# 02_ESP12_CORE.net
KiCad netlist of a schematic drawn in Altium Designer
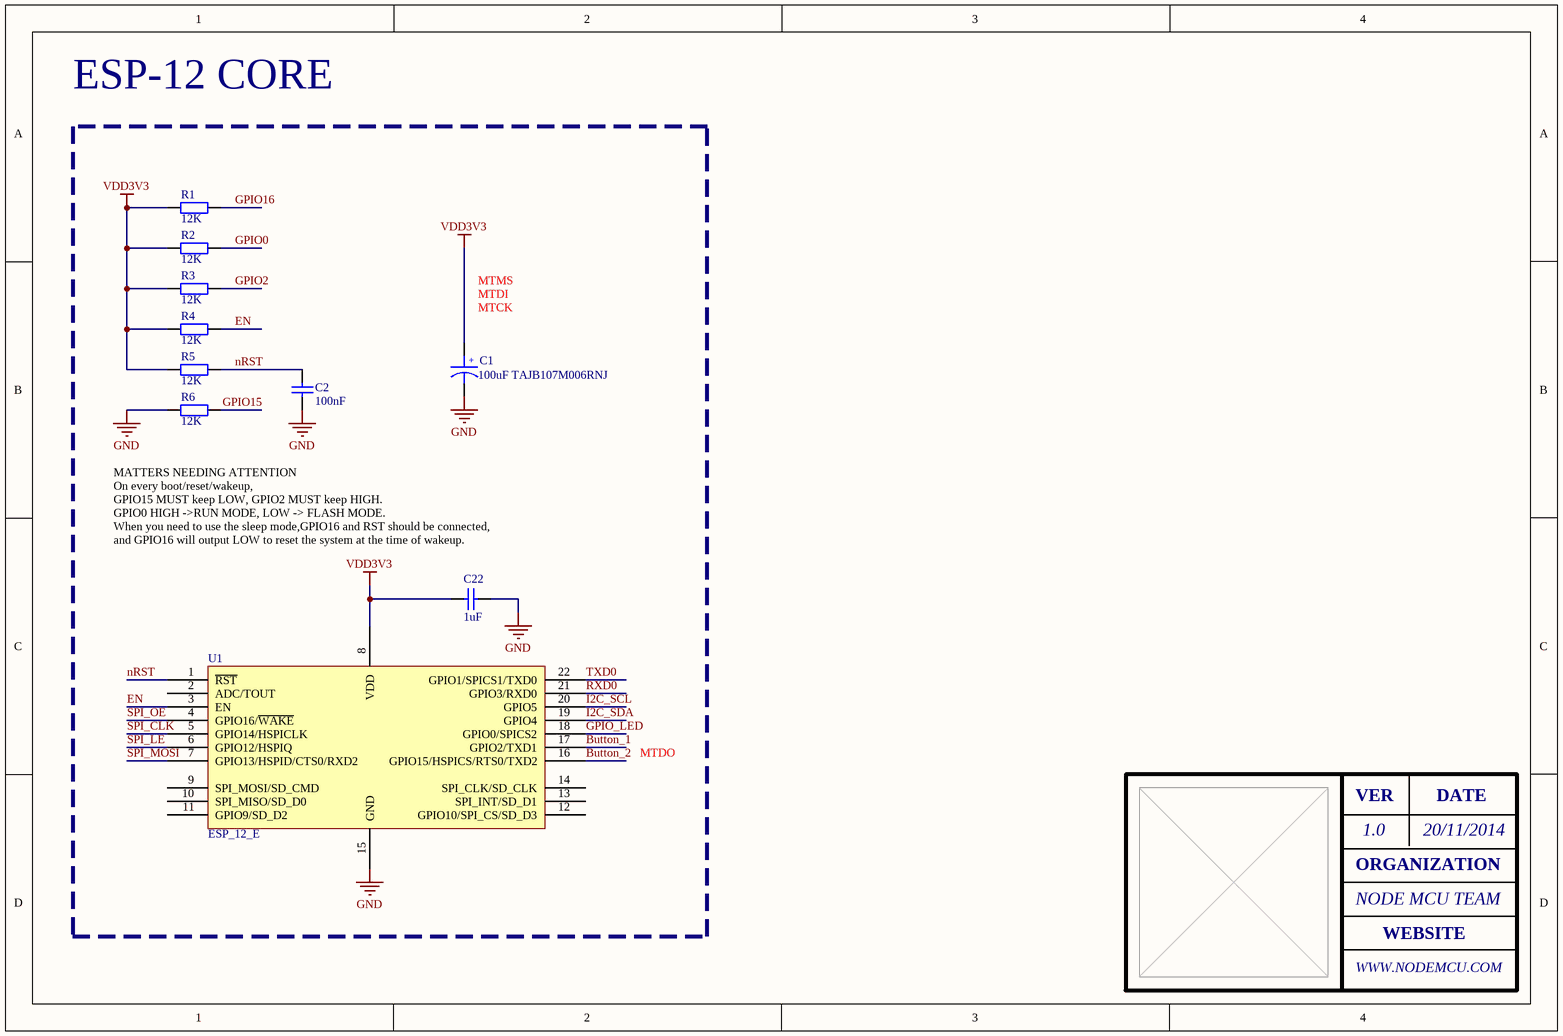
[diagram p0: 02_ESP12_CORE.SchDoc]

(export (version "E")
  (design (tool "Eeschema 10.0.6"))
  (components
    (comp (ref "C1")
      (value "100uF TAJB107M006RNJ")
      (footprint "FP_Tantal_D")
      (description "Capacitor, SM Tantalum; Body 3.5 x 2.8 mm (LxW typ)")
      (libsource (lib "Vowstar_Basic_Device") (part "SMT_C_Tantalum_B"))
    )
    (comp (ref "C2")
      (value "100nF")
      (footprint "FP_0805_CAP_085")
      (description "Capacitor")
      (fields (field (name "TOLERANCE") "+80%/-20%") (field (name "VOLTAGE") "25V"))
      (libsource (lib "onlablib") (part "CAP 100nF"))
    )
    (comp (ref "C22")
      (value "1uF")
      (footprint "6-0805_M")
      (description "Capacitor")
      (fields (field (name "TOLERANCE") "+80%/-20%") (field (name "VOLTAGE") "25V"))
      (libsource (lib "onlablib") (part "CAP 1uF"))
    )
    (comp (ref "R1")
      (value "12K")
      (footprint "FP_0805_RES")
      (description "Resistor")
      (fields (field (name "TOLERANCE") "5%") (field (name "POWER") "125mW"))
      (libsource (lib "onlablib") (part "RES 12K"))
    )
    (comp (ref "R2")
      (value "12K")
      (footprint "FP_0805_RES")
      (description "Resistor")
      (fields (field (name "TOLERANCE") "5%") (field (name "POWER") "125mW"))
      (libsource (lib "onlablib") (part "RES 12K"))
    )
    (comp (ref "R3")
      (value "12K")
      (footprint "FP_0805_RES")
      (description "Resistor")
      (fields (field (name "TOLERANCE") "5%") (field (name "POWER") "125mW"))
      (libsource (lib "onlablib") (part "RES 12K"))
    )
    (comp (ref "R4")
      (value "12K")
      (footprint "FP_0805_RES")
      (description "Resistor")
      (fields (field (name "TOLERANCE") "5%") (field (name "POWER") "125mW"))
      (libsource (lib "onlablib") (part "RES 12K"))
    )
    (comp (ref "R5")
      (value "12K")
      (footprint "FP_0805_RES")
      (description "Resistor")
      (fields (field (name "TOLERANCE") "5%") (field (name "POWER") "125mW"))
      (libsource (lib "onlablib") (part "RES 12K"))
    )
    (comp (ref "R6")
      (value "12K")
      (footprint "FP_0805_RES")
      (description "Resistor")
      (fields (field (name "TOLERANCE") "5%") (field (name "POWER") "125mW"))
      (libsource (lib "onlablib") (part "RES 12K"))
    )
    (comp (ref "U1")
      (value "ESP_12_E")
      (footprint "ESP_12_E _widepad")
      (description "ESP-12 Wi-Fi Module by AI-Thinker")
      (libsource (lib "Vowstar_Module") (part "ESP_12_E"))
    )
  )
  (nets
    (net (code "1") (name "/Button_1") (class "Default")
      (node (ref "U1") (pin "17") (pinfunction "GPIO2/TXD1_17") (pintype "passive"))
    )
    (net (code "2") (name "/Button_2") (class "Default")
      (node (ref "U1") (pin "16") (pinfunction "GPIO15/HSPICS/RTS0/TXD2_16") (pintype "passive"))
    )
    (net (code "3") (name "/EN") (class "Default")
      (node (ref "R4") (pin "2") (pinfunction "2_2") (pintype "passive"))
      (node (ref "U1") (pin "3") (pinfunction "EN_3") (pintype "passive"))
    )
    (net (code "4") (name "/GPIO0") (class "Default")
      (node (ref "R2") (pin "2") (pinfunction "2_2") (pintype "passive"))
    )
    (net (code "5") (name "/GPIO2") (class "Default")
      (node (ref "R3") (pin "2") (pinfunction "2_2") (pintype "passive"))
    )
    (net (code "6") (name "/GPIO15") (class "Default")
      (node (ref "R6") (pin "2") (pinfunction "2_2") (pintype "passive"))
    )
    (net (code "7") (name "/GPIO16") (class "Default")
      (node (ref "R1") (pin "2") (pinfunction "2_2") (pintype "passive"))
    )
    (net (code "8") (name "/GPIO_LED") (class "Default")
      (node (ref "U1") (pin "18") (pinfunction "GPIO0/SPICS2_18") (pintype "passive"))
    )
    (net (code "9") (name "/I2C_SCL") (class "Default")
      (node (ref "U1") (pin "20") (pinfunction "GPIO5_20") (pintype "passive"))
    )
    (net (code "10") (name "/I2C_SDA") (class "Default")
      (node (ref "U1") (pin "19") (pinfunction "GPIO4_19") (pintype "passive"))
    )
    (net (code "11") (name "/RXD0") (class "Default")
      (node (ref "U1") (pin "21") (pinfunction "GPIO3/RXD0_21") (pintype "passive"))
    )
    (net (code "12") (name "/SPI_CLK") (class "Default")
      (node (ref "U1") (pin "5") (pinfunction "GPIO14/HSPICLK_5") (pintype "passive"))
    )
    (net (code "13") (name "/SPI_LE") (class "Default")
      (node (ref "U1") (pin "6") (pinfunction "GPIO12/HSPIQ_6") (pintype "passive"))
    )
    (net (code "14") (name "/SPI_MOSI") (class "Default")
      (node (ref "U1") (pin "7") (pinfunction "GPIO13/HSPID/CTS0/RXD2_7") (pintype "passive"))
    )
    (net (code "15") (name "/SPI_OE") (class "Default")
      (node (ref "U1") (pin "4") (pinfunction "GPIO16/~{WAKE}_4") (pintype "passive"))
    )
    (net (code "16") (name "/TXD0") (class "Default")
      (node (ref "U1") (pin "22") (pinfunction "GPIO1/SPICS1/TXD0_22") (pintype "passive"))
    )
    (net (code "17") (name "/nRST") (class "Default")
      (node (ref "C2") (pin "2") (pinfunction "2_2") (pintype "passive"))
      (node (ref "R5") (pin "2") (pinfunction "2_2") (pintype "passive"))
      (node (ref "U1") (pin "1") (pinfunction "~{RST}_1") (pintype "passive"))
    )
    (net (code "18") (name "GND") (class "Default")
      (node (ref "C1") (pin "2") (pinfunction "2_2") (pintype "passive"))
      (node (ref "C2") (pin "1") (pinfunction "1_1") (pintype "passive"))
      (node (ref "C22") (pin "1") (pinfunction "1_1") (pintype "passive"))
      (node (ref "R6") (pin "1") (pinfunction "1_1") (pintype "passive"))
      (node (ref "U1") (pin "15") (pinfunction "GND_15") (pintype "passive"))
    )
    (net (code "19") (name "VDD3V3") (class "Default")
      (node (ref "C1") (pin "1") (pinfunction "1_1") (pintype "passive"))
      (node (ref "C22") (pin "2") (pinfunction "2_2") (pintype "passive"))
      (node (ref "R1") (pin "1") (pinfunction "1_1") (pintype "passive"))
      (node (ref "R2") (pin "1") (pinfunction "1_1") (pintype "passive"))
      (node (ref "R3") (pin "1") (pinfunction "1_1") (pintype "passive"))
      (node (ref "R4") (pin "1") (pinfunction "1_1") (pintype "passive"))
      (node (ref "R5") (pin "1") (pinfunction "1_1") (pintype "passive"))
      (node (ref "U1") (pin "8") (pinfunction "VDD_8") (pintype "passive"))
    )
    (net (code "20") (name "unconnected-(U1-ADC{slash}TOUT-Pad2)") (class "Default")
      (node (ref "U1") (pin "2") (pinfunction "ADC/TOUT_2") (pintype "passive"))
    )
    (net (code "21") (name "unconnected-(U1-GPIO9{slash}SD_D2-Pad11)") (class "Default")
      (node (ref "U1") (pin "11") (pinfunction "GPIO9/SD_D2_11") (pintype "passive"))
    )
    (net (code "22") (name "unconnected-(U1-GPIO10{slash}SPI_CS{slash}SD_D3-Pad12)") (class "Default")
      (node (ref "U1") (pin "12") (pinfunction "GPIO10/SPI_CS/SD_D3_12") (pintype "passive"))
    )
    (net (code "23") (name "unconnected-(U1-SPI_CLK{slash}SD_CLK-Pad14)") (class "Default")
      (node (ref "U1") (pin "14") (pinfunction "SPI_CLK/SD_CLK_14") (pintype "passive"))
    )
    (net (code "24") (name "unconnected-(U1-SPI_INT{slash}SD_D1-Pad13)") (class "Default")
      (node (ref "U1") (pin "13") (pinfunction "SPI_INT/SD_D1_13") (pintype "passive"))
    )
    (net (code "25") (name "unconnected-(U1-SPI_MISO{slash}SD_D0-Pad10)") (class "Default")
      (node (ref "U1") (pin "10") (pinfunction "SPI_MISO/SD_D0_10") (pintype "passive"))
    )
    (net (code "26") (name "unconnected-(U1-SPI_MOSI{slash}SD_CMD-Pad9)") (class "Default")
      (node (ref "U1") (pin "9") (pinfunction "SPI_MOSI/SD_CMD_9") (pintype "passive"))
    )
  )
)
